# APP_1_Ethernet_m.net
KiCad netlist of a schematic drawn in Altium Designer
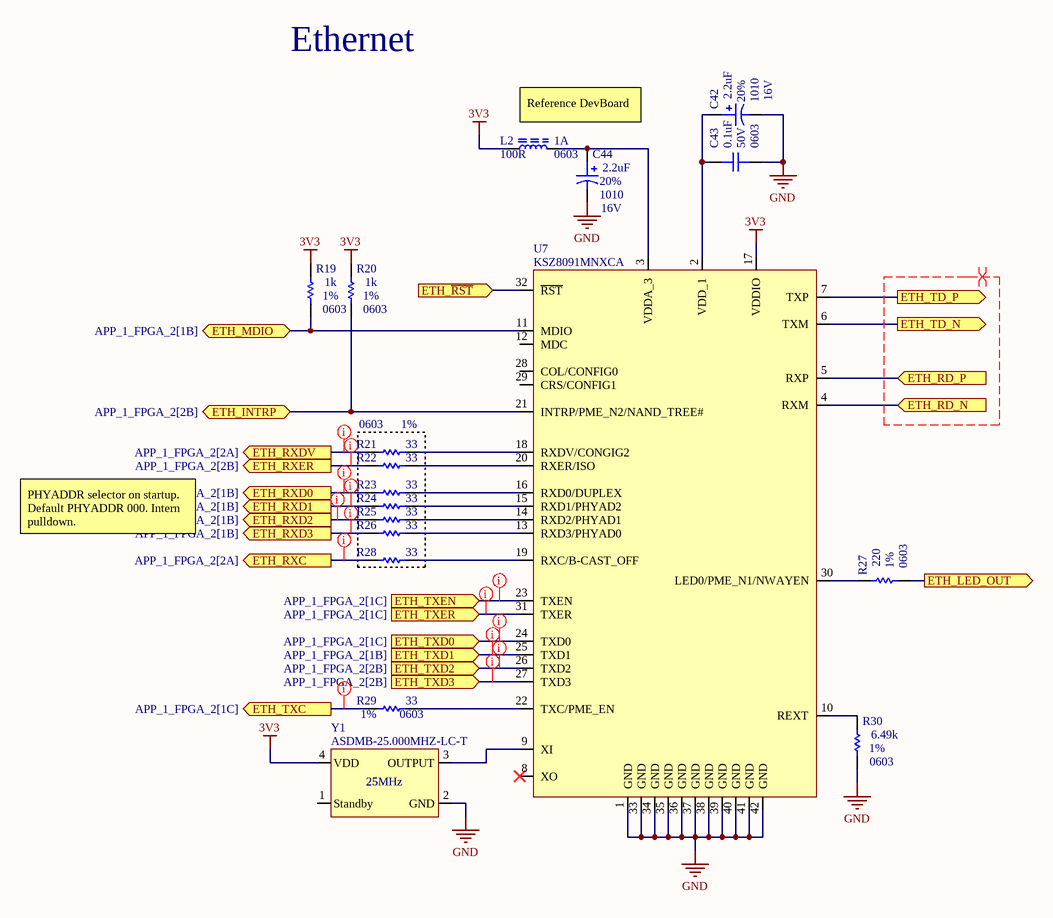
[diagram p0: APP_1_Ethernet_m.SchDoc]

(export (version "E")
  (design (tool "Eeschema 10.0.6"))
  (components
    (comp (ref "C42")
      (value "2.2uF")
      (footprint "CAP_ALU_1010_vishay")
      (description "CAP - ALU 330uF 20% 16V - 1010")
      (fields
        (field (name "MFG") "Vishay Dale")
        (field (name "MFG PART NUMBER") "MAL214699501E3")
        (field (name "VOLTAGE") "16V")
        (field (name "PACKAGE") "1010")
        (field (name "PRECISION") "20%")
        (field (name "CREATEDBY") "Jonathan Bouchard")
      )
      (libsource (lib "S7CAS_LIB2023") (part "CAP_ALU_MAL214699501E3"))
    )
    (comp (ref "C43")
      (value "0.1uF")
      (footprint "CAP_0603")
      (description "CAP - 0603")
      (fields
        (field (name "VOLTAGE") "50V")
        (field (name "PACKAGE") "0603")
        (field (name "CREATEDBY") "Jonathan Bouchard")
      )
      (libsource (lib "S7CAS_LIB2023") (part "CAP - 0603"))
    )
    (comp (ref "C44")
      (value "2.2uF")
      (footprint "CAP_ALU_1010_vishay")
      (description "CAP - ALU 330uF 20% 16V - 1010")
      (fields
        (field (name "MFG") "Vishay Dale")
        (field (name "MFG PART NUMBER") "MAL214699501E3")
        (field (name "VOLTAGE") "16V")
        (field (name "PACKAGE") "1010")
        (field (name "PRECISION") "20%")
        (field (name "CREATEDBY") "Jonathan Bouchard")
      )
      (libsource (lib "S7CAS_LIB2023") (part "CAP_ALU_MAL214699501E3"))
    )
    (comp (ref "L2")
      (value "100R")
      (footprint "FER_0603")
      (description "FER - 0603")
      (fields
        (field (name "CURRENT") "1A")
        (field (name "PACKAGE") "0603")
        (field (name "CREATEDBY") "Jonathan Bouchard")
      )
      (libsource (lib "S7CAS_LIB2023") (part "FER - 0603"))
    )
    (comp (ref "R19")
      (value "1k")
      (footprint "RES_0603")
      (description "RES - 0603")
      (fields
        (field (name "PACKAGE") "0603")
        (field (name "PRECISION") "1%")
        (field (name "CREATEDBY") "Jonathan Bouchard")
      )
      (libsource (lib "S7CAS_LIB2023") (part "RES - 0603"))
    )
    (comp (ref "R20")
      (value "1k")
      (footprint "RES_0603")
      (description "RES - 0603")
      (fields
        (field (name "PACKAGE") "0603")
        (field (name "PRECISION") "1%")
        (field (name "CREATEDBY") "Jonathan Bouchard")
      )
      (libsource (lib "S7CAS_LIB2023") (part "RES - 0603"))
    )
    (comp (ref "R21")
      (value "33")
      (footprint "RES_0603")
      (description "RES - 0603")
      (fields
        (field (name "PACKAGE") "0603")
        (field (name "PRECISION") "1%")
        (field (name "CREATEDBY") "Jonathan Bouchard")
      )
      (libsource (lib "S7CAS_LIB2023") (part "RES - 0603"))
    )
    (comp (ref "R22")
      (value "33")
      (footprint "RES_0603")
      (description "RES - 0603")
      (fields (field (name "CREATEDBY") "Jonathan Bouchard"))
      (libsource (lib "S7CAS_LIB2023") (part "RES - 0603"))
    )
    (comp (ref "R23")
      (value "33")
      (footprint "RES_0603")
      (description "RES - 0603")
      (fields (field (name "CREATEDBY") "Jonathan Bouchard"))
      (libsource (lib "S7CAS_LIB2023") (part "RES - 0603"))
    )
    (comp (ref "R24")
      (value "33")
      (footprint "RES_0603")
      (description "RES - 0603")
      (fields (field (name "CREATEDBY") "Jonathan Bouchard"))
      (libsource (lib "S7CAS_LIB2023") (part "RES - 0603"))
    )
    (comp (ref "R25")
      (value "33")
      (footprint "RES_0603")
      (description "RES - 0603")
      (fields (field (name "CREATEDBY") "Jonathan Bouchard"))
      (libsource (lib "S7CAS_LIB2023") (part "RES - 0603"))
    )
    (comp (ref "R26")
      (value "33")
      (footprint "RES_0603")
      (description "RES - 0603")
      (fields (field (name "CREATEDBY") "Jonathan Bouchard"))
      (libsource (lib "S7CAS_LIB2023") (part "RES - 0603"))
    )
    (comp (ref "R27")
      (value "220")
      (footprint "RES_0603")
      (description "RES - 0603")
      (fields
        (field (name "PACKAGE") "0603")
        (field (name "PRECISION") "1%")
        (field (name "CREATEDBY") "Jonathan Bouchard")
      )
      (libsource (lib "S7CAS_LIB2023") (part "RES - 0603"))
    )
    (comp (ref "R28")
      (value "33")
      (footprint "RES_0603")
      (description "RES - 0603")
      (fields (field (name "CREATEDBY") "Jonathan Bouchard"))
      (libsource (lib "S7CAS_LIB2023") (part "RES - 0603"))
    )
    (comp (ref "R29")
      (value "33")
      (footprint "RES_0603")
      (description "RES - 0603")
      (fields
        (field (name "PACKAGE") "0603")
        (field (name "PRECISION") "1%")
        (field (name "CREATEDBY") "Jonathan Bouchard")
      )
      (libsource (lib "S7CAS_LIB2023") (part "RES - 0603"))
    )
    (comp (ref "R30")
      (value "6.49k")
      (footprint "RES_0603")
      (description "RES - 0603")
      (fields
        (field (name "PACKAGE") "0603")
        (field (name "PRECISION") "1%")
        (field (name "CREATEDBY") "Jonathan Bouchard")
      )
      (libsource (lib "S7CAS_LIB2023") (part "RES - 0603"))
    )
    (comp (ref "U7")
      (value "KSZ8091MNXCA")
      (footprint "COM_ETH_PHY_KSZ8091MNXCA")
      (description "COM - ETHERNET PHY 10/100 - QFN-32")
      (fields
        (field (name "VOLTAGE") "1.8V, 2.5V, 3.3V")
        (field (name "MFG") "Micrel")
        (field (name "CREATEDBY") "Jonathan Bouchard")
      )
      (libsource (lib "S7CAS_LIB2023") (part "COM_ETH_PHY_KSZ8091MNXCA"))
    )
    (comp (ref "Y1")
      (value "ASDMB-25.000MHZ-LC-T")
      (footprint "OSC_ASDMB-25.000MHZ-LC-T")
      (description "OSC - 25MHz XO (Standard) LVCMOS - 4-SMD, No Lead")
      (fields
        (field (name "TOLERANCE") "±50ppm")
        (field (name "CREATEDBY/DATE") "Joël Lemay 2019-03-29")
        (field (name "VERIFIEDBY") "C. Paulin - 29 mai 2019")
      )
      (libsource (lib "S7CAS_LIB2023") (part "OSC_ASDMB-25.000MHZ-LC-T"))
    )
  )
  (nets
    (net (code "1") (name "/ETH_INTRP") (class "Default")
      (node (ref "R20") (pin "1") (pinfunction "1_1") (pintype "passive"))
      (node (ref "U7") (pin "21") (pinfunction "INTRP/PME_N2/NAND_TREE#_21") (pintype "passive"))
    )
    (net (code "2") (name "/ETH_LED_OUT") (class "Default")
      (node (ref "R27") (pin "1") (pinfunction "1_1") (pintype "passive"))
    )
    (net (code "3") (name "/ETH_MDIO") (class "Default")
      (node (ref "R19") (pin "1") (pinfunction "1_1") (pintype "passive"))
      (node (ref "U7") (pin "11") (pinfunction "MDIO_11") (pintype "passive"))
    )
    (net (code "4") (name "/ETH_RD_N") (class "Default")
      (node (ref "U7") (pin "4") (pinfunction "RXM_4") (pintype "passive"))
    )
    (net (code "5") (name "/ETH_RD_P") (class "Default")
      (node (ref "U7") (pin "5") (pinfunction "RXP_5") (pintype "passive"))
    )
    (net (code "6") (name "/ETH_RXC") (class "Default")
      (node (ref "R28") (pin "2") (pinfunction "2_2") (pintype "passive"))
    )
    (net (code "7") (name "/ETH_RXD0") (class "Default")
      (node (ref "R23") (pin "2") (pinfunction "2_2") (pintype "passive"))
    )
    (net (code "8") (name "/ETH_RXD1") (class "Default")
      (node (ref "R24") (pin "2") (pinfunction "2_2") (pintype "passive"))
    )
    (net (code "9") (name "/ETH_RXD2") (class "Default")
      (node (ref "R25") (pin "2") (pinfunction "2_2") (pintype "passive"))
    )
    (net (code "10") (name "/ETH_RXD3") (class "Default")
      (node (ref "R26") (pin "2") (pinfunction "2_2") (pintype "passive"))
    )
    (net (code "11") (name "/ETH_RXDV") (class "Default")
      (node (ref "R21") (pin "2") (pinfunction "2_2") (pintype "passive"))
    )
    (net (code "12") (name "/ETH_RXER") (class "Default")
      (node (ref "R22") (pin "2") (pinfunction "2_2") (pintype "passive"))
    )
    (net (code "13") (name "/ETH_TD_N") (class "Default")
      (node (ref "U7") (pin "6") (pinfunction "TXM_6") (pintype "passive"))
    )
    (net (code "14") (name "/ETH_TD_P") (class "Default")
      (node (ref "U7") (pin "7") (pinfunction "TXP_7") (pintype "passive"))
    )
    (net (code "15") (name "/ETH_TXC") (class "Default")
      (node (ref "R29") (pin "2") (pinfunction "2_2") (pintype "passive"))
    )
    (net (code "16") (name "/ETH_TXD0") (class "Default")
      (node (ref "U7") (pin "24") (pinfunction "TXD0_24") (pintype "passive"))
    )
    (net (code "17") (name "/ETH_TXD1") (class "Default")
      (node (ref "U7") (pin "25") (pinfunction "TXD1_25") (pintype "passive"))
    )
    (net (code "18") (name "/ETH_TXD2") (class "Default")
      (node (ref "U7") (pin "26") (pinfunction "TXD2_26") (pintype "passive"))
    )
    (net (code "19") (name "/ETH_TXD3") (class "Default")
      (node (ref "U7") (pin "27") (pinfunction "TXD3_27") (pintype "passive"))
    )
    (net (code "20") (name "/ETH_TXEN") (class "Default")
      (node (ref "U7") (pin "23") (pinfunction "TXEN_23") (pintype "passive"))
    )
    (net (code "21") (name "/ETH_TXER") (class "Default")
      (node (ref "U7") (pin "31") (pinfunction "TXER_31") (pintype "passive"))
    )
    (net (code "22") (name "/ETH_~{RST}") (class "Default")
      (node (ref "U7") (pin "32") (pinfunction "RST_32") (pintype "passive"))
    )
    (net (code "23") (name "3V3") (class "Default")
      (node (ref "L2") (pin "2") (pinfunction "2_2") (pintype "passive"))
      (node (ref "R19") (pin "2") (pinfunction "2_2") (pintype "passive"))
      (node (ref "R20") (pin "2") (pinfunction "2_2") (pintype "passive"))
      (node (ref "U7") (pin "17") (pinfunction "VDDIO_17") (pintype "power_in"))
      (node (ref "Y1") (pin "4") (pinfunction "VDD_4") (pintype "passive"))
    )
    (net (code "24") (name "GND") (class "Default")
      (node (ref "C42") (pin "2") (pinfunction "2_2") (pintype "passive"))
      (node (ref "C43") (pin "1") (pinfunction "1_1") (pintype "passive"))
      (node (ref "C44") (pin "2") (pinfunction "2_2") (pintype "passive"))
      (node (ref "R30") (pin "1") (pinfunction "1_1") (pintype "passive"))
      (node (ref "U7") (pin "1") (pinfunction "GND_1") (pintype "passive"))
      (node (ref "U7") (pin "33") (pinfunction "GND_33") (pintype "passive"))
      (node (ref "U7") (pin "34") (pinfunction "GND_34") (pintype "passive"))
      (node (ref "U7") (pin "35") (pinfunction "GND_35") (pintype "passive"))
      (node (ref "U7") (pin "36") (pinfunction "GND_36") (pintype "passive"))
      (node (ref "U7") (pin "37") (pinfunction "GND_37") (pintype "passive"))
      (node (ref "U7") (pin "38") (pinfunction "GND_38") (pintype "passive"))
      (node (ref "U7") (pin "39") (pinfunction "GND_39") (pintype "passive"))
      (node (ref "U7") (pin "40") (pinfunction "GND_40") (pintype "passive"))
      (node (ref "U7") (pin "41") (pinfunction "GND_41") (pintype "passive"))
      (node (ref "U7") (pin "42") (pinfunction "GND_42") (pintype "passive"))
      (node (ref "Y1") (pin "2") (pinfunction "GND_2") (pintype "passive"))
    )
    (net (code "25") (name "Net-(U7-LED0{slash}PME_N1{slash}NWAYEN)") (class "Default")
      (node (ref "R27") (pin "2") (pinfunction "2_2") (pintype "passive"))
      (node (ref "U7") (pin "30") (pinfunction "LED0/PME_N1/NWAYEN_30") (pintype "passive"))
    )
    (net (code "26") (name "Net-(U7-REXT)") (class "Default")
      (node (ref "R30") (pin "2") (pinfunction "2_2") (pintype "passive"))
      (node (ref "U7") (pin "10") (pinfunction "REXT_10") (pintype "passive"))
    )
    (net (code "27") (name "Net-(U7-RXC{slash}B-CAST_OFF)") (class "Default")
      (node (ref "R28") (pin "1") (pinfunction "1_1") (pintype "passive"))
      (node (ref "U7") (pin "19") (pinfunction "RXC/B-CAST_OFF_19") (pintype "passive"))
    )
    (net (code "28") (name "Net-(U7-RXD0{slash}DUPLEX)") (class "Default")
      (node (ref "R23") (pin "1") (pinfunction "1_1") (pintype "passive"))
      (node (ref "U7") (pin "16") (pinfunction "RXD0/DUPLEX_16") (pintype "passive"))
    )
    (net (code "29") (name "Net-(U7-RXD1{slash}PHYAD2)") (class "Default")
      (node (ref "R24") (pin "1") (pinfunction "1_1") (pintype "passive"))
      (node (ref "U7") (pin "15") (pinfunction "RXD1/PHYAD2_15") (pintype "passive"))
    )
    (net (code "30") (name "Net-(U7-RXD2{slash}PHYAD1)") (class "Default")
      (node (ref "R25") (pin "1") (pinfunction "1_1") (pintype "passive"))
      (node (ref "U7") (pin "14") (pinfunction "RXD2/PHYAD1_14") (pintype "passive"))
    )
    (net (code "31") (name "Net-(U7-RXD3{slash}PHYAD0)") (class "Default")
      (node (ref "R26") (pin "1") (pinfunction "1_1") (pintype "passive"))
      (node (ref "U7") (pin "13") (pinfunction "RXD3/PHYAD0_13") (pintype "passive"))
    )
    (net (code "32") (name "Net-(U7-RXDV{slash}CONGIG2)") (class "Default")
      (node (ref "R21") (pin "1") (pinfunction "1_1") (pintype "passive"))
      (node (ref "U7") (pin "18") (pinfunction "RXDV/CONGIG2_18") (pintype "passive"))
    )
    (net (code "33") (name "Net-(U7-RXER{slash}ISO)") (class "Default")
      (node (ref "R22") (pin "1") (pinfunction "1_1") (pintype "passive"))
      (node (ref "U7") (pin "20") (pinfunction "RXER/ISO_20") (pintype "passive"))
    )
    (net (code "34") (name "Net-(U7-TXC{slash}PME_EN)") (class "Default")
      (node (ref "R29") (pin "1") (pinfunction "1_1") (pintype "passive"))
      (node (ref "U7") (pin "22") (pinfunction "TXC/PME_EN_22") (pintype "passive"))
    )
    (net (code "35") (name "Net-(U7-VDDA_3)") (class "Default")
      (node (ref "C44") (pin "1") (pinfunction "1_1") (pintype "passive"))
      (node (ref "L2") (pin "1") (pinfunction "1_1") (pintype "passive"))
      (node (ref "U7") (pin "3") (pinfunction "VDDA_3_3") (pintype "power_in"))
    )
    (net (code "36") (name "Net-(U7-VDD_1)") (class "Default")
      (node (ref "C42") (pin "1") (pinfunction "1_1") (pintype "passive"))
      (node (ref "C43") (pin "2") (pinfunction "2_2") (pintype "passive"))
      (node (ref "U7") (pin "2") (pinfunction "VDD_1_2") (pintype "power_in"))
    )
    (net (code "37") (name "Net-(U7-XI)") (class "Default")
      (node (ref "U7") (pin "9") (pinfunction "XI_9") (pintype "passive"))
      (node (ref "Y1") (pin "3") (pinfunction "OUTPUT_3") (pintype "passive"))
    )
    (net (code "38") (name "unconnected-(U7-COL{slash}CONFIG0-Pad28)") (class "Default")
      (node (ref "U7") (pin "28") (pinfunction "COL/CONFIG0_28") (pintype "passive"))
    )
    (net (code "39") (name "unconnected-(U7-CRS{slash}CONFIG1-Pad29)") (class "Default")
      (node (ref "U7") (pin "29") (pinfunction "CRS/CONFIG1_29") (pintype "passive"))
    )
    (net (code "40") (name "unconnected-(U7-MDC-Pad12)") (class "Default")
      (node (ref "U7") (pin "12") (pinfunction "MDC_12") (pintype "passive"))
    )
    (net (code "41") (name "unconnected-(U7-XO-Pad8)") (class "Default")
      (node (ref "U7") (pin "8") (pinfunction "XO_8") (pintype "passive+no_connect"))
    )
    (net (code "42") (name "unconnected-(Y1-Standby-Pad1)") (class "Default")
      (node (ref "Y1") (pin "1") (pinfunction "Standby_1") (pintype "passive"))
    )
  )
)
